# AT86RF233_RPI_2.net
KiCad netlist of a schematic drawn in EAGLE
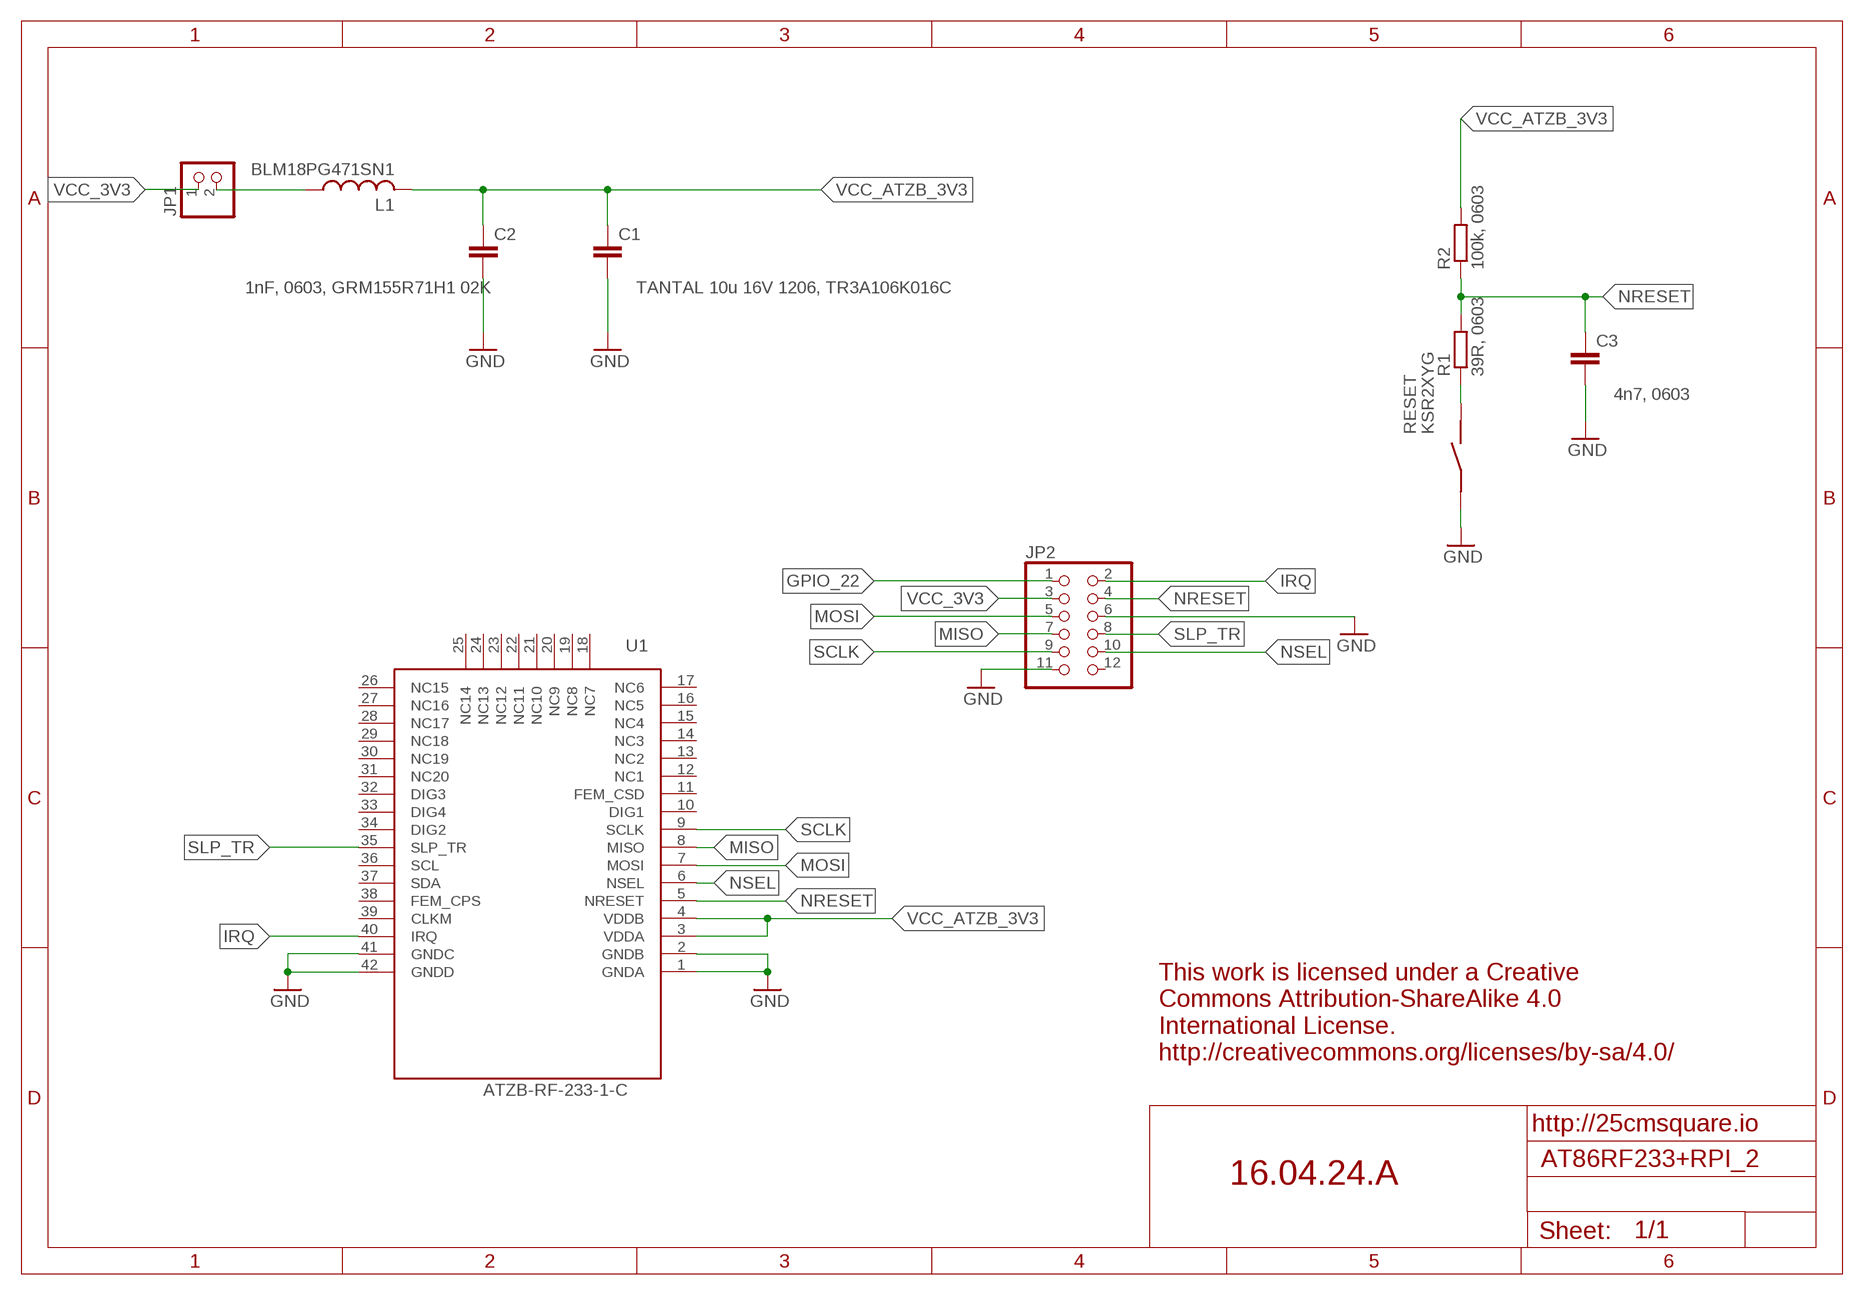
[diagram p0: schematic, sheet 1]

(export (version "E")
  (design (tool "Eeschema 10.0.6"))
  (components
    (comp (ref "C1")
      (value "TANTAL 10u 16V 1206, TR3A106K016C")
      (footprint "eagle-import:C1206K")
      (libsource (lib "eagle-import") (part "resistor_C-EUC1206K"))
    )
    (comp (ref "C2")
      (value "1nF, 0603, GRM155R71H1 02K")
      (footprint "eagle-import:C0603K")
      (libsource (lib "eagle-import") (part "C-EUC0603K"))
    )
    (comp (ref "C3")
      (value "4n7, 0603")
      (footprint "eagle-import:C0603K")
      (libsource (lib "eagle-import") (part "C-EUC0603K"))
    )
    (comp (ref "JP1")
      (value "PINHD-1X2")
      (footprint "eagle-import:1X02")
      (libsource (lib "eagle-import") (part "PINHD-1X2"))
    )
    (comp (ref "JP2")
      (value "PINHD-2X6")
      (footprint "eagle-import:2X06")
      (libsource (lib "eagle-import") (part "PINHD-2X6"))
    )
    (comp (ref "L1")
      (value "BLM18PG471SN1")
      (footprint "eagle-import:L0603")
      (libsource (lib "eagle-import") (part "L0603(1608)"))
    )
    (comp (ref "R1")
      (value "39R, 0603")
      (footprint "eagle-import:R0603")
      (libsource (lib "eagle-import") (part "R-EU_R0603"))
    )
    (comp (ref "R2")
      (value "100k, 0603")
      (footprint "eagle-import:R0603")
      (libsource (lib "eagle-import") (part "R-EU_R0603"))
    )
    (comp (ref "RESET")
      (value "KSR2XYG")
      (footprint "eagle-import:KSR2XYG")
      (libsource (lib "eagle-import") (part "KSR2XYG"))
    )
    (comp (ref "U1")
      (value "ATZB-RF-233-1-C")
      (footprint "eagle-import:ATZB-RF-233-1-C")
      (libsource (lib "eagle-import") (part "ATZB-RF-233-1-C"))
    )
  )
  (nets
    (net (code "1") (name "GND") (class "Default")
      (node (ref "C1") (pin "2") (pinfunction "2_2") (pintype "passive"))
      (node (ref "C2") (pin "2") (pinfunction "2_2") (pintype "passive"))
      (node (ref "C3") (pin "2") (pinfunction "2_2") (pintype "passive"))
      (node (ref "JP2") (pin "11") (pinfunction "11_11") (pintype "passive"))
      (node (ref "JP2") (pin "6") (pinfunction "6_6") (pintype "passive"))
      (node (ref "RESET") (pin "P$2") (pinfunction "2_P$2") (pintype "passive"))
      (node (ref "U1") (pin "1") (pinfunction "GNDA_1") (pintype "bidirectional"))
      (node (ref "U1") (pin "2") (pinfunction "GNDB_2") (pintype "bidirectional"))
      (node (ref "U1") (pin "41") (pinfunction "GNDC_41") (pintype "bidirectional"))
      (node (ref "U1") (pin "42") (pinfunction "GNDD_42") (pintype "bidirectional"))
    )
    (net (code "2") (name "GPIO_22") (class "Default")
      (node (ref "JP2") (pin "1") (pinfunction "1_1") (pintype "passive"))
    )
    (net (code "3") (name "IRQ") (class "Default")
      (node (ref "JP2") (pin "2") (pinfunction "2_2") (pintype "passive"))
      (node (ref "U1") (pin "40") (pinfunction "IRQ_40") (pintype "bidirectional"))
    )
    (net (code "4") (name "MISO") (class "Default")
      (node (ref "JP2") (pin "7") (pinfunction "7_7") (pintype "passive"))
      (node (ref "U1") (pin "8") (pinfunction "MISO_8") (pintype "bidirectional"))
    )
    (net (code "5") (name "MOSI") (class "Default")
      (node (ref "JP2") (pin "5") (pinfunction "5_5") (pintype "passive"))
      (node (ref "U1") (pin "7") (pinfunction "MOSI_7") (pintype "bidirectional"))
    )
    (net (code "6") (name "NRESET") (class "Default")
      (node (ref "C3") (pin "1") (pinfunction "1_1") (pintype "passive"))
      (node (ref "JP2") (pin "4") (pinfunction "4_4") (pintype "passive"))
      (node (ref "R1") (pin "2") (pinfunction "2_2") (pintype "passive"))
      (node (ref "R2") (pin "1") (pinfunction "1_1") (pintype "passive"))
      (node (ref "U1") (pin "5") (pinfunction "NRESET_5") (pintype "bidirectional"))
    )
    (net (code "7") (name "NSEL") (class "Default")
      (node (ref "JP2") (pin "10") (pinfunction "10_10") (pintype "passive"))
      (node (ref "U1") (pin "6") (pinfunction "NSEL_6") (pintype "bidirectional"))
    )
    (net (code "8") (name "Net-(JP1-Pad2)") (class "Default")
      (node (ref "JP1") (pin "2") (pinfunction "2_2") (pintype "passive"))
      (node (ref "L1") (pin "1") (pinfunction "1_1") (pintype "passive"))
    )
    (net (code "9") (name "Net-(RESET-1)") (class "Default")
      (node (ref "R1") (pin "1") (pinfunction "1_1") (pintype "passive"))
      (node (ref "RESET") (pin "P$1") (pinfunction "1_P$1") (pintype "passive"))
    )
    (net (code "10") (name "SCLK") (class "Default")
      (node (ref "JP2") (pin "9") (pinfunction "9_9") (pintype "passive"))
      (node (ref "U1") (pin "9") (pinfunction "SCLK_9") (pintype "bidirectional"))
    )
    (net (code "11") (name "SLP_TR") (class "Default")
      (node (ref "JP2") (pin "8") (pinfunction "8_8") (pintype "passive"))
      (node (ref "U1") (pin "35") (pinfunction "SLP_TR_35") (pintype "bidirectional"))
    )
    (net (code "12") (name "VCC_3V3") (class "Default")
      (node (ref "JP1") (pin "1") (pinfunction "1_1") (pintype "passive"))
      (node (ref "JP2") (pin "3") (pinfunction "3_3") (pintype "passive"))
    )
    (net (code "13") (name "VCC_ATZB_3V3") (class "Default")
      (node (ref "C1") (pin "1") (pinfunction "1_1") (pintype "passive"))
      (node (ref "C2") (pin "1") (pinfunction "1_1") (pintype "passive"))
      (node (ref "L1") (pin "2") (pinfunction "2_2") (pintype "passive"))
      (node (ref "R2") (pin "2") (pinfunction "2_2") (pintype "passive"))
      (node (ref "U1") (pin "3") (pinfunction "VDDA_3") (pintype "bidirectional"))
      (node (ref "U1") (pin "4") (pinfunction "VDDB_4") (pintype "bidirectional"))
    )
    (net (code "14") (name "unconnected-(JP2-Pad12)") (class "Default")
      (node (ref "JP2") (pin "12") (pinfunction "12_12") (pintype "passive"))
    )
    (net (code "15") (name "unconnected-(U1-CLKM-Pad39)") (class "Default")
      (node (ref "U1") (pin "39") (pinfunction "CLKM_39") (pintype "bidirectional"))
    )
    (net (code "16") (name "unconnected-(U1-DIG1-Pad10)") (class "Default")
      (node (ref "U1") (pin "10") (pinfunction "DIG1_10") (pintype "bidirectional"))
    )
    (net (code "17") (name "unconnected-(U1-DIG2-Pad34)") (class "Default")
      (node (ref "U1") (pin "34") (pinfunction "DIG2_34") (pintype "bidirectional"))
    )
    (net (code "18") (name "unconnected-(U1-DIG3-Pad32)") (class "Default")
      (node (ref "U1") (pin "32") (pinfunction "DIG3_32") (pintype "bidirectional"))
    )
    (net (code "19") (name "unconnected-(U1-DIG4-Pad33)") (class "Default")
      (node (ref "U1") (pin "33") (pinfunction "DIG4_33") (pintype "bidirectional"))
    )
    (net (code "20") (name "unconnected-(U1-FEM_CPS-Pad38)") (class "Default")
      (node (ref "U1") (pin "38") (pinfunction "FEM_CPS_38") (pintype "bidirectional"))
    )
    (net (code "21") (name "unconnected-(U1-FEM_CSD-Pad11)") (class "Default")
      (node (ref "U1") (pin "11") (pinfunction "FEM_CSD_11") (pintype "bidirectional"))
    )
    (net (code "22") (name "unconnected-(U1-NC1-Pad12)") (class "Default")
      (node (ref "U1") (pin "12") (pinfunction "NC1_12") (pintype "bidirectional"))
    )
    (net (code "23") (name "unconnected-(U1-NC2-Pad13)") (class "Default")
      (node (ref "U1") (pin "13") (pinfunction "NC2_13") (pintype "bidirectional"))
    )
    (net (code "24") (name "unconnected-(U1-NC3-Pad14)") (class "Default")
      (node (ref "U1") (pin "14") (pinfunction "NC3_14") (pintype "bidirectional"))
    )
    (net (code "25") (name "unconnected-(U1-NC4-Pad15)") (class "Default")
      (node (ref "U1") (pin "15") (pinfunction "NC4_15") (pintype "bidirectional"))
    )
    (net (code "26") (name "unconnected-(U1-NC5-Pad16)") (class "Default")
      (node (ref "U1") (pin "16") (pinfunction "NC5_16") (pintype "bidirectional"))
    )
    (net (code "27") (name "unconnected-(U1-NC6-Pad17)") (class "Default")
      (node (ref "U1") (pin "17") (pinfunction "NC6_17") (pintype "bidirectional"))
    )
    (net (code "28") (name "unconnected-(U1-NC7-Pad18)") (class "Default")
      (node (ref "U1") (pin "18") (pinfunction "NC7_18") (pintype "bidirectional"))
    )
    (net (code "29") (name "unconnected-(U1-NC8-Pad19)") (class "Default")
      (node (ref "U1") (pin "19") (pinfunction "NC8_19") (pintype "bidirectional"))
    )
    (net (code "30") (name "unconnected-(U1-NC9-Pad20)") (class "Default")
      (node (ref "U1") (pin "20") (pinfunction "NC9_20") (pintype "bidirectional"))
    )
    (net (code "31") (name "unconnected-(U1-NC10-Pad21)") (class "Default")
      (node (ref "U1") (pin "21") (pinfunction "NC10_21") (pintype "bidirectional"))
    )
    (net (code "32") (name "unconnected-(U1-NC11-Pad22)") (class "Default")
      (node (ref "U1") (pin "22") (pinfunction "NC11_22") (pintype "bidirectional"))
    )
    (net (code "33") (name "unconnected-(U1-NC12-Pad23)") (class "Default")
      (node (ref "U1") (pin "23") (pinfunction "NC12_23") (pintype "bidirectional"))
    )
    (net (code "34") (name "unconnected-(U1-NC13-Pad24)") (class "Default")
      (node (ref "U1") (pin "24") (pinfunction "NC13_24") (pintype "bidirectional"))
    )
    (net (code "35") (name "unconnected-(U1-NC14-Pad25)") (class "Default")
      (node (ref "U1") (pin "25") (pinfunction "NC14_25") (pintype "bidirectional"))
    )
    (net (code "36") (name "unconnected-(U1-NC15-Pad26)") (class "Default")
      (node (ref "U1") (pin "26") (pinfunction "NC15_26") (pintype "bidirectional"))
    )
    (net (code "37") (name "unconnected-(U1-NC16-Pad27)") (class "Default")
      (node (ref "U1") (pin "27") (pinfunction "NC16_27") (pintype "bidirectional"))
    )
    (net (code "38") (name "unconnected-(U1-NC17-Pad28)") (class "Default")
      (node (ref "U1") (pin "28") (pinfunction "NC17_28") (pintype "bidirectional"))
    )
    (net (code "39") (name "unconnected-(U1-NC18-Pad29)") (class "Default")
      (node (ref "U1") (pin "29") (pinfunction "NC18_29") (pintype "bidirectional"))
    )
    (net (code "40") (name "unconnected-(U1-NC19-Pad30)") (class "Default")
      (node (ref "U1") (pin "30") (pinfunction "NC19_30") (pintype "bidirectional"))
    )
    (net (code "41") (name "unconnected-(U1-NC20-Pad31)") (class "Default")
      (node (ref "U1") (pin "31") (pinfunction "NC20_31") (pintype "bidirectional"))
    )
    (net (code "42") (name "unconnected-(U1-SCL-Pad36)") (class "Default")
      (node (ref "U1") (pin "36") (pinfunction "SCL_36") (pintype "bidirectional"))
    )
    (net (code "43") (name "unconnected-(U1-SDA-Pad37)") (class "Default")
      (node (ref "U1") (pin "37") (pinfunction "SDA_37") (pintype "bidirectional"))
    )
  )
)
